# Photocoupler12Vinput_2pin.net
KiCad netlist of a schematic drawn in Altium Designer
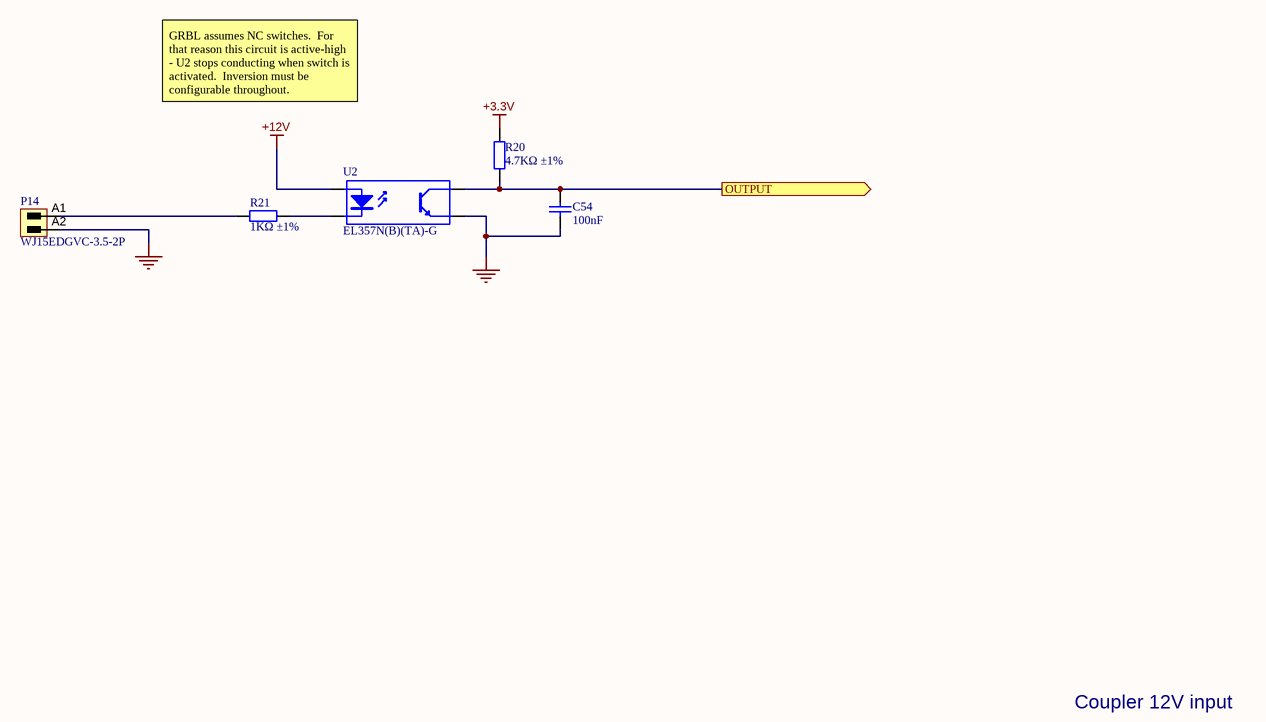
[diagram p0: Photocoupler12Vinput_2pin.SchDoc]

(export (version "E")
  (design (tool "Eeschema 10.0.6"))
  (components
    (comp (ref "C54")
      (value "100nF")
      (footprint "0402_C")
      (description "Chip capacitors")
      (fields
        (field (name "MANUFACTURER") "Samsung Electro-Mechanics")
        (field (name "PARTNUMBER") "CL05B104KO5NNNC")
      )
      (libsource (lib "Cap") (part "0402 100nF (104) 10% 16V"))
    )
    (comp (ref "P14")
      (value "WJ15EDGVC-3.5-2P")
      (footprint "SL_3_50_180G_02")
      (fields (field (name "MANUFACTURER") "Weidmueller"))
      (libsource (lib "PrintNC_GRBLHAL_Breakout") (part "Header_Male_02_1x02"))
    )
    (comp (ref "R20")
      (value "4.7KΩ ±1%")
      (footprint "0402_R")
      (description "Chip resistor")
      (fields (field (name "MANUFACTURER") "Uniroyal Elec") (field (name "PARTNUMBER") "0402WGF4701TCE"))
      (libsource (lib "RES") (part "0402 4.7K (4701) 1%"))
    )
    (comp (ref "R21")
      (value "1KΩ ±1%")
      (footprint "0402_R")
      (description "Chip resistor")
      (fields (field (name "MANUFACTURER") "Uniroyal Elec") (field (name "PARTNUMBER") "0402WGF1001TCE"))
      (libsource (lib "RES") (part "0402 1K (1001) 1%"))
    )
    (comp (ref "U2")
      (value "EL357N(B)(TA)-G")
      (footprint "SOP-4_P2.54")
      (description "贴片光耦")
      (libsource (lib "IC") (part "EL357N(B)(TA)-G_[C6649]"))
    )
  )
  (nets
    (net (code "1") (name "+3.3V") (class "Default")
      (node (ref "R20") (pin "2") (pinfunction "2_2") (pintype "passive"))
    )
    (net (code "2") (name "+12V") (class "Default")
      (node (ref "U2") (pin "1") (pinfunction "A_1") (pintype "passive"))
    )
    (net (code "3") (name "/OUTPUT") (class "Default")
      (node (ref "C54") (pin "2") (pinfunction "2_2") (pintype "passive"))
      (node (ref "R20") (pin "1") (pinfunction "1_1") (pintype "passive"))
      (node (ref "U2") (pin "4") (pinfunction "C_4") (pintype "passive"))
    )
    (net (code "4") (name "GND") (class "Default")
      (node (ref "C54") (pin "1") (pinfunction "1_1") (pintype "passive"))
      (node (ref "P14") (pin "A2") (pinfunction "A2_A2") (pintype "passive"))
      (node (ref "U2") (pin "3") (pinfunction "E_3") (pintype "passive"))
    )
    (net (code "5") (name "Net-(P14-PadA1)") (class "Default")
      (node (ref "P14") (pin "A1") (pinfunction "A1_A1") (pintype "passive"))
      (node (ref "R21") (pin "1") (pinfunction "1_1") (pintype "passive"))
    )
    (net (code "6") (name "Net-(U2-K)") (class "Default")
      (node (ref "R21") (pin "2") (pinfunction "2_2") (pintype "passive"))
      (node (ref "U2") (pin "2") (pinfunction "K_2") (pintype "passive"))
    )
  )
)
